# samd21_sensorhub_Lite_TQFP32_1_2_0_feb20.net
KiCad netlist of a schematic drawn in EAGLE
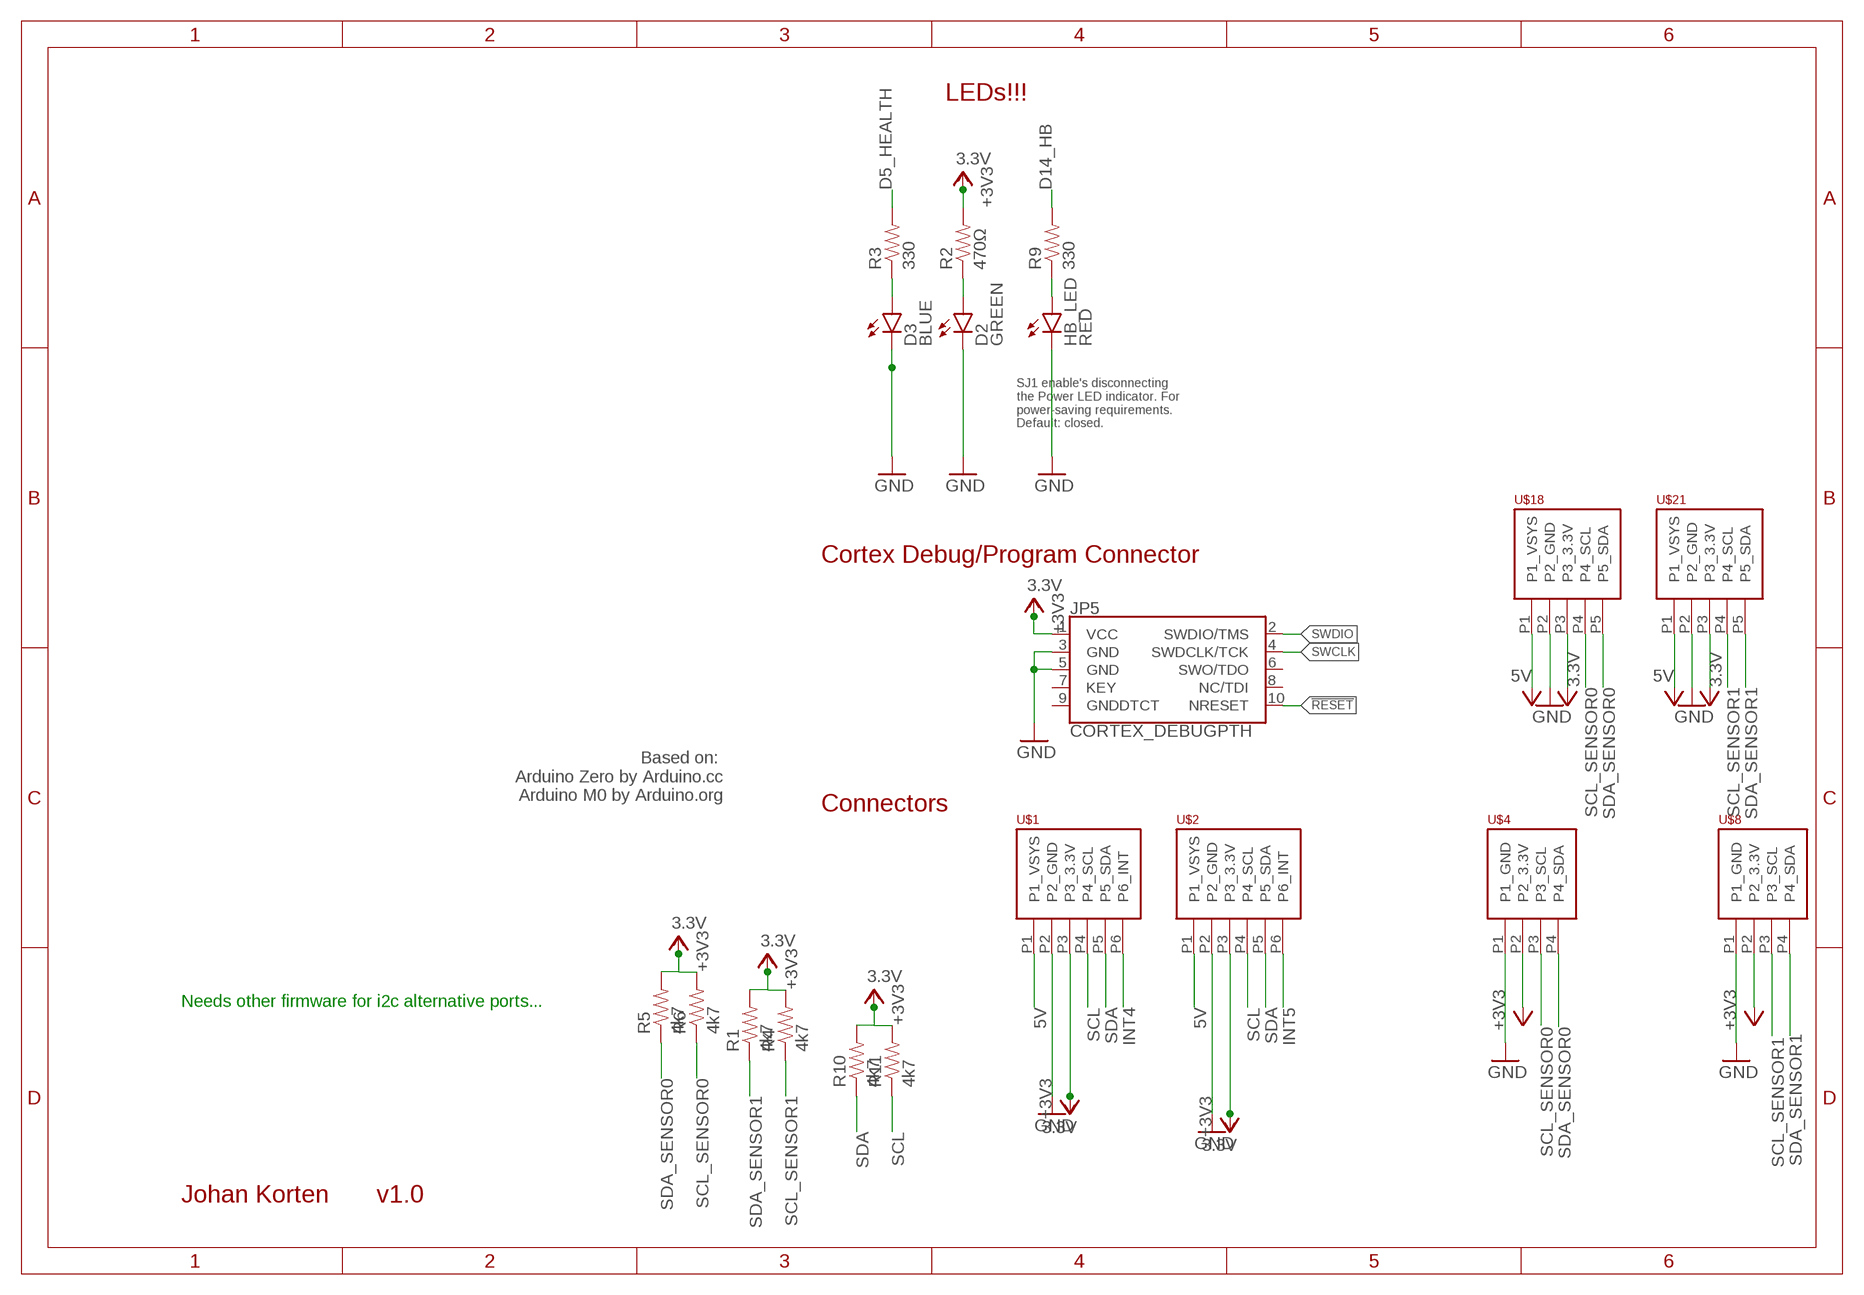
[diagram p0: schematic, sheet 1]
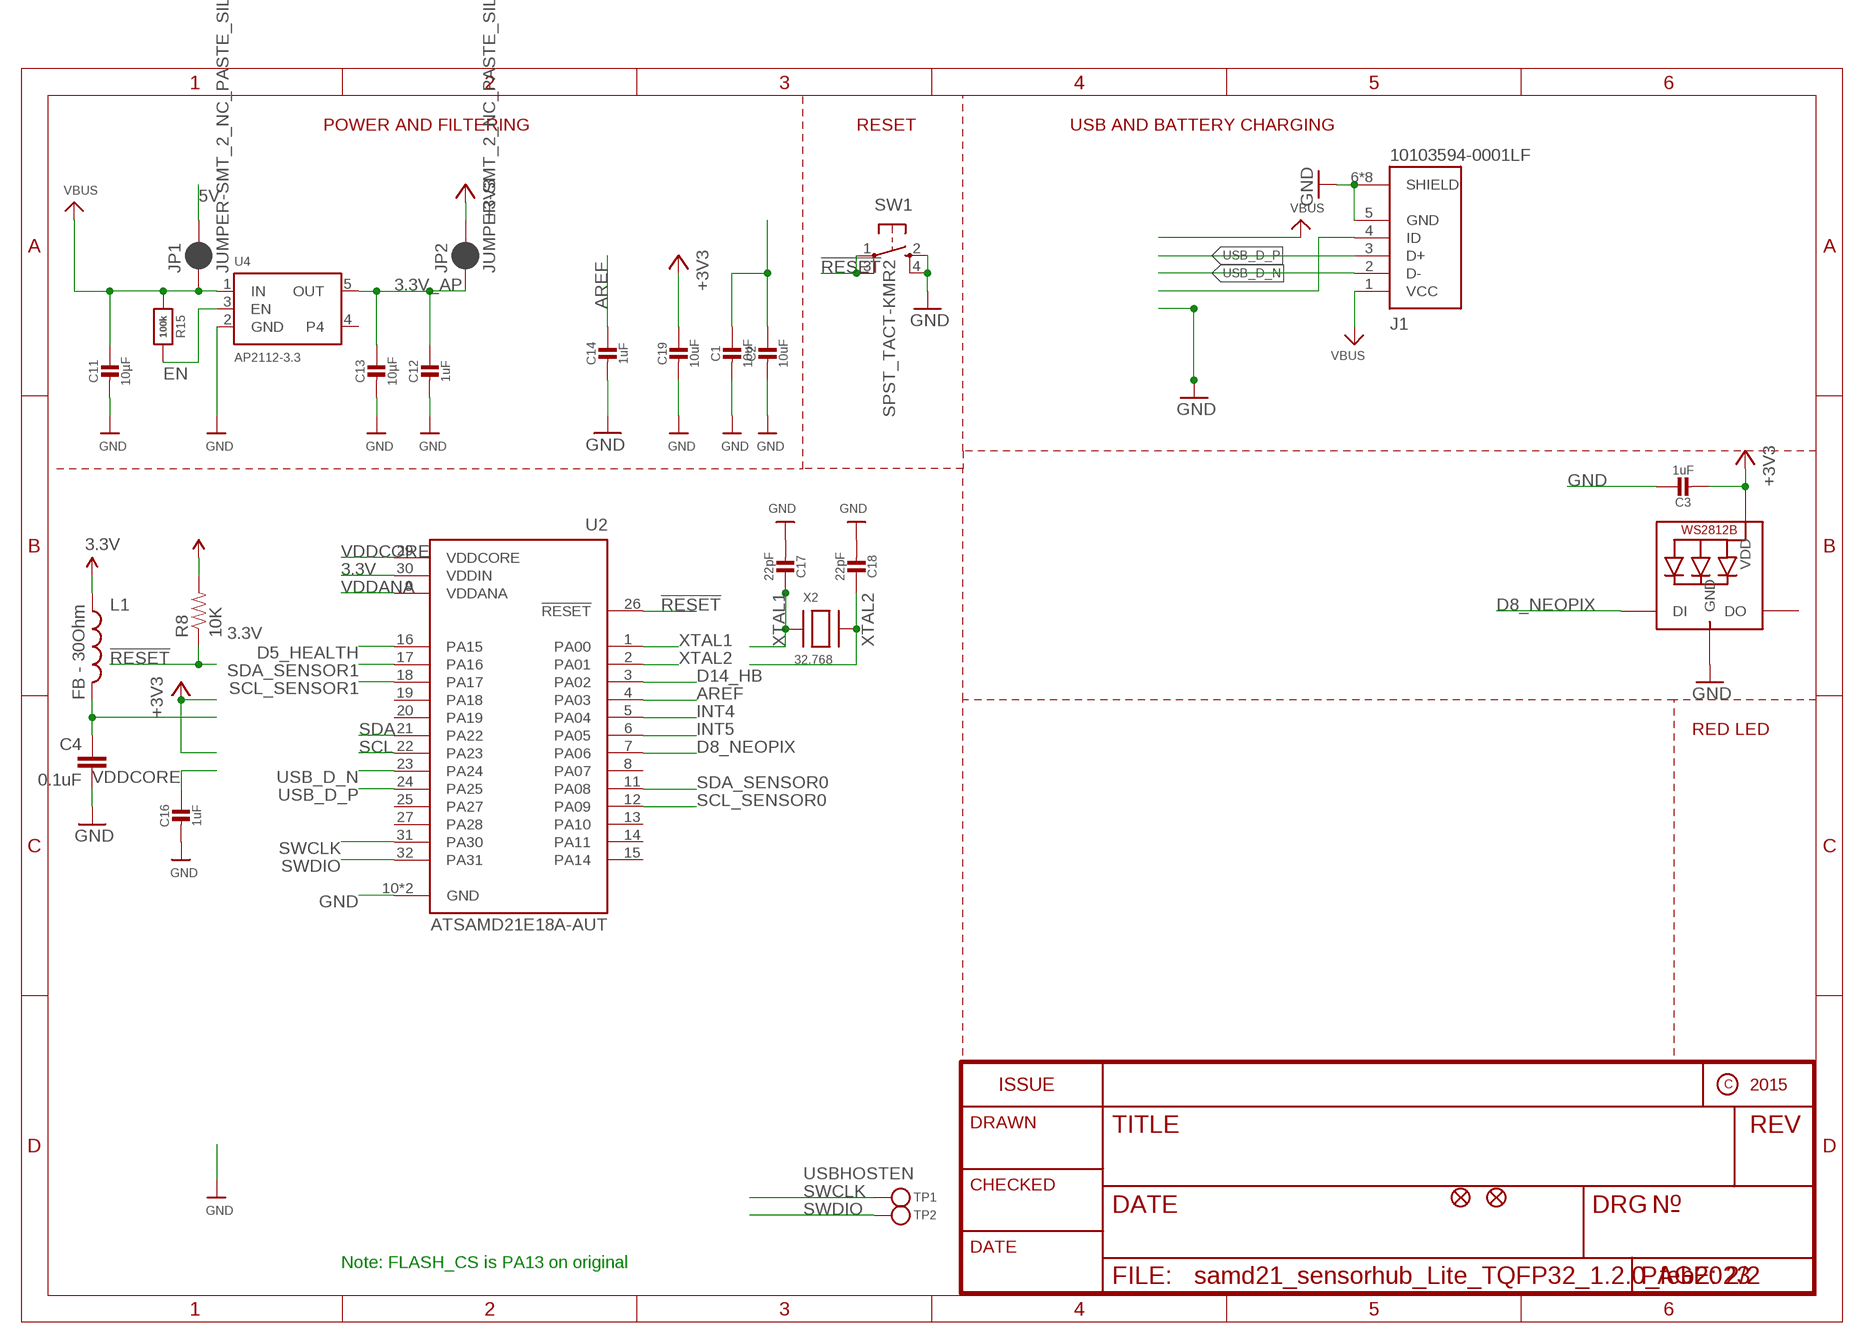
[diagram p1: schematic, sheet 2]

(export (version "E")
  (design (tool "Eeschema 10.0.6"))
  (components
    (comp (ref "C1")
      (value "10uF")
      (footprint "eagle-import:0805-NO")
      (libsource (lib "eagle-import") (part "CAP_CERAMIC0805-NOOUTLINE"))
    )
    (comp (ref "C2")
      (value "10uF")
      (footprint "eagle-import:0805-NO")
      (libsource (lib "eagle-import") (part "CAP_CERAMIC0805-NOOUTLINE"))
    )
    (comp (ref "C3")
      (value "1uF")
      (footprint "eagle-import:0603-NO")
      (libsource (lib "eagle-import") (part "CAP_CERAMIC0603_NO"))
    )
    (comp (ref "C4")
      (value "0.1uF")
      (footprint "eagle-import:0402-CAP")
      (libsource (lib "eagle-import") (part "0.1UF-16V(+-10%)(0402)"))
    )
    (comp (ref "C11")
      (value "10µF")
      (footprint "eagle-import:0805-NO")
      (libsource (lib "eagle-import") (part "CAP_CERAMIC0805-NOOUTLINE"))
    )
    (comp (ref "C12")
      (value "1uF")
      (footprint "eagle-import:0603-NO")
      (libsource (lib "eagle-import") (part "CAP_CERAMIC0603_NO"))
    )
    (comp (ref "C13")
      (value "10µF")
      (footprint "eagle-import:0805-NO")
      (libsource (lib "eagle-import") (part "CAP_CERAMIC0805-NOOUTLINE"))
    )
    (comp (ref "C14")
      (value "1uF")
      (footprint "eagle-import:0603-NO")
      (libsource (lib "eagle-import") (part "CAP_CERAMIC0603_NO"))
    )
    (comp (ref "C16")
      (value "1uF")
      (footprint "eagle-import:0603-NO")
      (libsource (lib "eagle-import") (part "CAP_CERAMIC0603_NO"))
    )
    (comp (ref "C17")
      (value "22pF")
      (footprint "eagle-import:0603-NO")
      (libsource (lib "eagle-import") (part "CAP_CERAMIC0603_NO"))
    )
    (comp (ref "C18")
      (value "22pF")
      (footprint "eagle-import:0603-NO")
      (libsource (lib "eagle-import") (part "CAP_CERAMIC0603_NO"))
    )
    (comp (ref "C19")
      (value "10uF")
      (footprint "eagle-import:0805-NO")
      (libsource (lib "eagle-import") (part "CAP_CERAMIC0805-NOOUTLINE"))
    )
    (comp (ref "J1")
      (value "10103594-0001LF")
      (footprint "eagle-import:AMPHENOL_10103594-0001LF")
      (fields (field (name "MF") "AMPHENOL ICC / FCI"))
      (libsource (lib "eagle-import") (part "10103594-0001LF"))
    )
    (comp (ref "JP1")
      (value "JUMPER-SMT_2_NC_PASTE_SILK")
      (footprint "eagle-import:SMT-JUMPER_2_NC_PASTE_SILK")
      (libsource (lib "eagle-import") (part "JUMPER-SMT_2_NC_PASTE_SILK"))
    )
    (comp (ref "JP2")
      (value "JUMPER-SMT_2_NC_PASTE_SILK")
      (footprint "eagle-import:SMT-JUMPER_2_NC_PASTE_SILK")
      (libsource (lib "eagle-import") (part "JUMPER-SMT_2_NC_PASTE_SILK"))
    )
    (comp (ref "L1")
      (value "FB - 30Ohm")
      (footprint "eagle-import:0603")
      (libsource (lib "eagle-import") (part "INDUCTOR0603"))
    )
    (comp (ref "LED1")
      (value "WS2812B3535")
      (footprint "eagle-import:LED3535")
      (libsource (lib "eagle-import") (part "WS2812B3535"))
    )
    (comp (ref "R8")
      (value "10K")
      (footprint "eagle-import:0603-RES")
      (libsource (lib "eagle-import") (part "10KOHM-1/10W-1%(0603)0603"))
    )
    (comp (ref "R15")
      (value "100k")
      (footprint "eagle-import:0603-NO")
      (libsource (lib "eagle-import") (part "RESISTOR_0603_NOOUT"))
    )
    (comp (ref "SW1")
      (value "SPST_TACT-KMR2")
      (footprint "eagle-import:KMR2")
      (libsource (lib "eagle-import") (part "SPST_TACT-KMR2"))
    )
    (comp (ref "TP1")
      (value "TESTPOINTROUND1.5MM")
      (footprint "eagle-import:TESTPOINT_ROUND_1.5MM")
      (libsource (lib "eagle-import") (part "TESTPOINTROUND1.5MM"))
    )
    (comp (ref "TP2")
      (value "TESTPOINTROUND1.5MM")
      (footprint "eagle-import:TESTPOINT_ROUND_1.5MM")
      (libsource (lib "eagle-import") (part "TESTPOINTROUND1.5MM"))
    )
    (comp (ref "U$34")
      (value "FIDUCIAL\"\"")
      (footprint "eagle-import:FIDUCIAL_1MM")
      (libsource (lib "eagle-import") (part "FIDUCIAL{dblquote}{dblquote}"))
    )
    (comp (ref "U$35")
      (value "FIDUCIAL\"\"")
      (footprint "eagle-import:FIDUCIAL_1MM")
      (libsource (lib "eagle-import") (part "FIDUCIAL{dblquote}{dblquote}"))
    )
    (comp (ref "U2")
      (value "ATSAMD21E18A-AUT")
      (footprint "eagle-import:QFP80P900X900X120-32N")
      (fields (field (name "MF") "Microchip") (field (name "MP") "ATSAMD21E18A-AU"))
      (libsource (lib "eagle-import") (part "ATSAMD21E18A-AUT"))
    )
    (comp (ref "U4")
      (value "AP2112-3.3")
      (footprint "eagle-import:SOT23-5")
      (libsource (lib "eagle-import") (part "VREG_SOT23-5"))
    )
    (comp (ref "X2")
      (value "32.768")
      (footprint "eagle-import:XTAL3215")
      (libsource (lib "eagle-import") (part "XTAL-3.2X1.5"))
    )
    (comp (ref "D2")
      (value "GREEN")
      (footprint "eagle-import:LED-0603")
      (libsource (lib "eagle-import") (part "LED-RED0603"))
    )
    (comp (ref "D3")
      (value "BLUE")
      (footprint "eagle-import:LED-0603")
      (libsource (lib "eagle-import") (part "LED-BLUE0603"))
    )
    (comp (ref "HB_LED")
      (value "RED")
      (footprint "eagle-import:LED-0603")
      (libsource (lib "eagle-import") (part "LED-RED0603"))
    )
    (comp (ref "JP5")
      (value "CORTEX_DEBUGPTH")
      (footprint "eagle-import:2X5-PTH-1.27MM")
      (libsource (lib "eagle-import") (part "CORTEX_DEBUGPTH"))
    )
    (comp (ref "R1")
      (value "4k7")
      (footprint "eagle-import:0603-RES")
      (libsource (lib "eagle-import") (part "330OHM1/10W1%(0603)"))
    )
    (comp (ref "R2")
      (value "470Ω")
      (footprint "eagle-import:0603-RES")
      (libsource (lib "eagle-import") (part "330OHM1/10W1%(0603)"))
    )
    (comp (ref "R3")
      (value "330")
      (footprint "eagle-import:0603-RES")
      (libsource (lib "eagle-import") (part "330OHM1/10W1%(0603)"))
    )
    (comp (ref "R4")
      (value "4k7")
      (footprint "eagle-import:0603-RES")
      (libsource (lib "eagle-import") (part "330OHM1/10W1%(0603)"))
    )
    (comp (ref "R5")
      (value "4k7")
      (footprint "eagle-import:0603-RES")
      (libsource (lib "eagle-import") (part "330OHM1/10W1%(0603)"))
    )
    (comp (ref "R6")
      (value "4k7")
      (footprint "eagle-import:0603-RES")
      (libsource (lib "eagle-import") (part "330OHM1/10W1%(0603)"))
    )
    (comp (ref "R9")
      (value "330")
      (footprint "eagle-import:0603-RES")
      (libsource (lib "eagle-import") (part "330OHM1/10W1%(0603)"))
    )
    (comp (ref "R10")
      (value "4k7")
      (footprint "eagle-import:0603-RES")
      (libsource (lib "eagle-import") (part "330OHM1/10W1%(0603)"))
    )
    (comp (ref "R11")
      (value "4k7")
      (footprint "eagle-import:0603-RES")
      (libsource (lib "eagle-import") (part "330OHM1/10W1%(0603)"))
    )
    (comp (ref "U$1")
      (value "PHOENIX_PTSM_M6_TH_I2CPPANGLE")
      (footprint "eagle-import:PTSM_M6_THRHOLE")
      (libsource (lib "eagle-import") (part "PHOENIX_PTSM_M6_TH_I2CPPANGLE"))
    )
    (comp (ref "U$2")
      (value "PHOENIX_PTSM_M6_TH_I2CPPANGLE")
      (footprint "eagle-import:PTSM_M6_THRHOLE")
      (libsource (lib "eagle-import") (part "PHOENIX_PTSM_M6_TH_I2CPPANGLE"))
    )
    (comp (ref "U$4")
      (value "PHOENIX_PTSM_M4_THANGLE")
      (footprint "eagle-import:PTSM_M4_TH")
      (libsource (lib "eagle-import") (part "PHOENIX_PTSM_M4_THANGLE"))
    )
    (comp (ref "U$8")
      (value "PHOENIX_PTSM_M4_THANGLE")
      (footprint "eagle-import:PTSM_M4_TH")
      (libsource (lib "eagle-import") (part "PHOENIX_PTSM_M4_THANGLE"))
    )
    (comp (ref "U$18")
      (value "PHOENIX_PTSM_M5_TH_I2C++")
      (footprint "eagle-import:PTSM_M5_THRHOLE")
      (libsource (lib "eagle-import") (part "PHOENIX_PTSM_M5_TH_I2C++"))
    )
    (comp (ref "U$21")
      (value "PHOENIX_PTSM_M5_TH_I2C++")
      (footprint "eagle-import:PTSM_M5_THRHOLE")
      (libsource (lib "eagle-import") (part "PHOENIX_PTSM_M5_TH_I2C++"))
    )
  )
  (nets
    (net (code "1") (name "3.3V") (class "Default")
      (node (ref "C19") (pin "1") (pinfunction "1_1") (pintype "passive"))
      (node (ref "C3") (pin "2") (pinfunction "2_2") (pintype "passive"))
      (node (ref "JP2") (pin "2") (pinfunction "2_2") (pintype "passive"))
      (node (ref "JP5") (pin "1") (pinfunction "VCC_1") (pintype "bidirectional"))
      (node (ref "L1") (pin "1") (pinfunction "1_1") (pintype "passive"))
      (node (ref "LED1") (pin "2") (pinfunction "VDD_2") (pintype "power_in"))
      (node (ref "R1") (pin "2") (pinfunction "2_2") (pintype "passive"))
      (node (ref "R10") (pin "2") (pinfunction "2_2") (pintype "passive"))
      (node (ref "R11") (pin "2") (pinfunction "2_2") (pintype "passive"))
      (node (ref "R2") (pin "2") (pinfunction "2_2") (pintype "passive"))
      (node (ref "R4") (pin "2") (pinfunction "2_2") (pintype "passive"))
      (node (ref "R5") (pin "2") (pinfunction "2_2") (pintype "passive"))
      (node (ref "R6") (pin "2") (pinfunction "2_2") (pintype "passive"))
      (node (ref "R8") (pin "2") (pinfunction "2_2") (pintype "passive"))
      (node (ref "U$1") (pin "P3") (pinfunction "P3_3.3V_P3") (pintype "power_in"))
      (node (ref "U$18") (pin "P3") (pinfunction "P3_3.3V_P3") (pintype "power_in"))
      (node (ref "U$2") (pin "P3") (pinfunction "P3_3.3V_P3") (pintype "power_in"))
      (node (ref "U$21") (pin "P3") (pinfunction "P3_3.3V_P3") (pintype "power_in"))
      (node (ref "U$4") (pin "P2") (pinfunction "P2_3.3V_P2") (pintype "power_in"))
      (node (ref "U$8") (pin "P2") (pinfunction "P2_3.3V_P2") (pintype "power_in"))
      (node (ref "U2") (pin "30") (pinfunction "VDDIN_30") (pintype "power_in"))
    )
    (net (code "2") (name "3.3V_AP") (class "Default")
      (node (ref "C12") (pin "1") (pinfunction "1_1") (pintype "passive"))
      (node (ref "C13") (pin "1") (pinfunction "1_1") (pintype "passive"))
      (node (ref "JP2") (pin "1") (pinfunction "1_1") (pintype "passive"))
      (node (ref "U4") (pin "5") (pinfunction "OUT_5") (pintype "power_in"))
    )
    (net (code "3") (name "5V") (class "Default")
      (node (ref "C1") (pin "1") (pinfunction "1_1") (pintype "passive"))
      (node (ref "C2") (pin "1") (pinfunction "1_1") (pintype "passive"))
      (node (ref "JP1") (pin "2") (pinfunction "2_2") (pintype "passive"))
      (node (ref "U$1") (pin "P1") (pinfunction "P1_VSYS_P1") (pintype "power_in"))
      (node (ref "U$18") (pin "P1") (pinfunction "P1_VSYS_P1") (pintype "power_in"))
      (node (ref "U$2") (pin "P1") (pinfunction "P1_VSYS_P1") (pintype "power_in"))
      (node (ref "U$21") (pin "P1") (pinfunction "P1_VSYS_P1") (pintype "power_in"))
    )
    (net (code "4") (name "AREF") (class "Default")
      (node (ref "C14") (pin "1") (pinfunction "1_1") (pintype "passive"))
      (node (ref "U2") (pin "4") (pinfunction "PA03_4") (pintype "bidirectional"))
    )
    (net (code "5") (name "D5_HEALTH") (class "Default")
      (node (ref "R3") (pin "2") (pinfunction "2_2") (pintype "passive"))
      (node (ref "U2") (pin "16") (pinfunction "PA15_16") (pintype "bidirectional"))
    )
    (net (code "6") (name "D8_NEOPIX") (class "Default")
      (node (ref "LED1") (pin "1") (pinfunction "DI_1") (pintype "input"))
      (node (ref "U2") (pin "7") (pinfunction "PA06_7") (pintype "bidirectional"))
    )
    (net (code "7") (name "D14_HB") (class "Default")
      (node (ref "R9") (pin "2") (pinfunction "2_2") (pintype "passive"))
      (node (ref "U2") (pin "3") (pinfunction "PA02_3") (pintype "bidirectional"))
    )
    (net (code "8") (name "EN") (class "Default")
      (node (ref "R15") (pin "2") (pinfunction "2_2") (pintype "passive"))
      (node (ref "U4") (pin "3") (pinfunction "EN_3") (pintype "input"))
    )
    (net (code "9") (name "GND") (class "Default")
      (node (ref "C1") (pin "2") (pinfunction "2_2") (pintype "passive"))
      (node (ref "C11") (pin "2") (pinfunction "2_2") (pintype "passive"))
      (node (ref "C12") (pin "2") (pinfunction "2_2") (pintype "passive"))
      (node (ref "C13") (pin "2") (pinfunction "2_2") (pintype "passive"))
      (node (ref "C14") (pin "2") (pinfunction "2_2") (pintype "passive"))
      (node (ref "C16") (pin "2") (pinfunction "2_2") (pintype "passive"))
      (node (ref "C17") (pin "2") (pinfunction "2_2") (pintype "passive"))
      (node (ref "C18") (pin "2") (pinfunction "2_2") (pintype "passive"))
      (node (ref "C19") (pin "2") (pinfunction "2_2") (pintype "passive"))
      (node (ref "C2") (pin "2") (pinfunction "2_2") (pintype "passive"))
      (node (ref "C3") (pin "1") (pinfunction "1_1") (pintype "passive"))
      (node (ref "C4") (pin "2") (pinfunction "2_2") (pintype "passive"))
      (node (ref "D2") (pin "C") (pinfunction "C_C") (pintype "passive"))
      (node (ref "D3") (pin "C") (pinfunction "C_C") (pintype "passive"))
      (node (ref "HB_LED") (pin "C") (pinfunction "C_C") (pintype "passive"))
      (node (ref "J1") (pin "10") (pinfunction "SHIELD_10") (pintype "passive"))
      (node (ref "J1") (pin "11") (pinfunction "SHIELD_11") (pintype "passive"))
      (node (ref "J1") (pin "5") (pinfunction "GND_5") (pintype "power_in"))
      (node (ref "J1") (pin "6") (pinfunction "SHIELD_6") (pintype "passive"))
      (node (ref "J1") (pin "7") (pinfunction "SHIELD_7") (pintype "passive"))
      (node (ref "J1") (pin "8") (pinfunction "SHIELD_8") (pintype "passive"))
      (node (ref "J1") (pin "9") (pinfunction "SHIELD_9") (pintype "passive"))
      (node (ref "J1") (pin "S1") (pinfunction "SHIELD_S1") (pintype "passive"))
      (node (ref "J1") (pin "S2") (pinfunction "SHIELD_S2") (pintype "passive"))
      (node (ref "JP5") (pin "3") (pinfunction "GND_3") (pintype "bidirectional"))
      (node (ref "JP5") (pin "5") (pinfunction "GND_5") (pintype "bidirectional"))
      (node (ref "LED1") (pin "4") (pinfunction "GND_4") (pintype "power_in"))
      (node (ref "SW1") (pin "2") (pinfunction "S_2") (pintype "passive"))
      (node (ref "SW1") (pin "4") (pinfunction "S1_4") (pintype "passive"))
      (node (ref "U$1") (pin "P2") (pinfunction "P2_GND_P2") (pintype "power_in"))
      (node (ref "U$18") (pin "P2") (pinfunction "P2_GND_P2") (pintype "power_in"))
      (node (ref "U$2") (pin "P2") (pinfunction "P2_GND_P2") (pintype "power_in"))
      (node (ref "U$21") (pin "P2") (pinfunction "P2_GND_P2") (pintype "power_in"))
      (node (ref "U$4") (pin "P1") (pinfunction "P1_GND_P1") (pintype "power_in"))
      (node (ref "U$8") (pin "P1") (pinfunction "P1_GND_P1") (pintype "power_in"))
      (node (ref "U2") (pin "10") (pinfunction "GND_10") (pintype "power_in"))
      (node (ref "U2") (pin "28") (pinfunction "GND_28") (pintype "power_in"))
      (node (ref "U4") (pin "2") (pinfunction "GND_2") (pintype "power_in"))
    )
    (net (code "10") (name "INT4") (class "Default")
      (node (ref "U$1") (pin "P6") (pinfunction "P6_INT_P6") (pintype "power_in"))
      (node (ref "U2") (pin "5") (pinfunction "PA04_5") (pintype "bidirectional"))
    )
    (net (code "11") (name "INT5") (class "Default")
      (node (ref "U$2") (pin "P6") (pinfunction "P6_INT_P6") (pintype "power_in"))
      (node (ref "U2") (pin "6") (pinfunction "PA05_6") (pintype "bidirectional"))
    )
    (net (code "12") (name "Net-(D2-PadA)") (class "Default")
      (node (ref "D2") (pin "A") (pinfunction "A_A") (pintype "passive"))
      (node (ref "R2") (pin "1") (pinfunction "1_1") (pintype "passive"))
    )
    (net (code "13") (name "Net-(D3-PadA)") (class "Default")
      (node (ref "D3") (pin "A") (pinfunction "A_A") (pintype "passive"))
      (node (ref "R3") (pin "1") (pinfunction "1_1") (pintype "passive"))
    )
    (net (code "14") (name "Net-(HB_LED-PadA)") (class "Default")
      (node (ref "HB_LED") (pin "A") (pinfunction "A_A") (pintype "passive"))
      (node (ref "R9") (pin "1") (pinfunction "1_1") (pintype "passive"))
    )
    (net (code "15") (name "SCL") (class "Default")
      (node (ref "R11") (pin "1") (pinfunction "1_1") (pintype "passive"))
      (node (ref "U$1") (pin "P4") (pinfunction "P4_SCL_P4") (pintype "bidirectional"))
      (node (ref "U$2") (pin "P4") (pinfunction "P4_SCL_P4") (pintype "bidirectional"))
      (node (ref "U2") (pin "22") (pinfunction "PA23_22") (pintype "bidirectional"))
    )
    (net (code "16") (name "SCL_SENSOR0") (class "Default")
      (node (ref "R6") (pin "1") (pinfunction "1_1") (pintype "passive"))
      (node (ref "U$18") (pin "P4") (pinfunction "P4_SCL_P4") (pintype "bidirectional"))
      (node (ref "U$4") (pin "P3") (pinfunction "P3_SCL_P3") (pintype "bidirectional"))
      (node (ref "U2") (pin "12") (pinfunction "PA09_12") (pintype "bidirectional"))
    )
    (net (code "17") (name "SCL_SENSOR1") (class "Default")
      (node (ref "R4") (pin "1") (pinfunction "1_1") (pintype "passive"))
      (node (ref "U$21") (pin "P4") (pinfunction "P4_SCL_P4") (pintype "bidirectional"))
      (node (ref "U$8") (pin "P3") (pinfunction "P3_SCL_P3") (pintype "bidirectional"))
      (node (ref "U2") (pin "18") (pinfunction "PA17_18") (pintype "bidirectional"))
    )
    (net (code "18") (name "SDA") (class "Default")
      (node (ref "R10") (pin "1") (pinfunction "1_1") (pintype "passive"))
      (node (ref "U$1") (pin "P5") (pinfunction "P5_SDA_P5") (pintype "bidirectional"))
      (node (ref "U$2") (pin "P5") (pinfunction "P5_SDA_P5") (pintype "bidirectional"))
      (node (ref "U2") (pin "21") (pinfunction "PA22_21") (pintype "bidirectional"))
    )
    (net (code "19") (name "SDA_SENSOR0") (class "Default")
      (node (ref "R5") (pin "1") (pinfunction "1_1") (pintype "passive"))
      (node (ref "U$18") (pin "P5") (pinfunction "P5_SDA_P5") (pintype "bidirectional"))
      (node (ref "U$4") (pin "P4") (pinfunction "P4_SDA_P4") (pintype "bidirectional"))
      (node (ref "U2") (pin "11") (pinfunction "PA08_11") (pintype "bidirectional"))
    )
    (net (code "20") (name "SDA_SENSOR1") (class "Default")
      (node (ref "R1") (pin "1") (pinfunction "1_1") (pintype "passive"))
      (node (ref "U$21") (pin "P5") (pinfunction "P5_SDA_P5") (pintype "bidirectional"))
      (node (ref "U$8") (pin "P4") (pinfunction "P4_SDA_P4") (pintype "bidirectional"))
      (node (ref "U2") (pin "17") (pinfunction "PA16_17") (pintype "bidirectional"))
    )
    (net (code "21") (name "SWCLK") (class "Default")
      (node (ref "JP5") (pin "4") (pinfunction "SWDCLK/TCK_4") (pintype "bidirectional"))
      (node (ref "TP1") (pin "P$1") (pinfunction "P$1_P$1") (pintype "bidirectional"))
      (node (ref "U2") (pin "31") (pinfunction "PA30_31") (pintype "bidirectional"))
    )
    (net (code "22") (name "SWDIO") (class "Default")
      (node (ref "JP5") (pin "2") (pinfunction "SWDIO/TMS_2") (pintype "bidirectional"))
      (node (ref "TP2") (pin "P$1") (pinfunction "P$1_P$1") (pintype "bidirectional"))
      (node (ref "U2") (pin "32") (pinfunction "PA31_32") (pintype "bidirectional"))
    )
    (net (code "23") (name "USB_D_N") (class "Default")
      (node (ref "J1") (pin "2") (pinfunction "D-_2") (pintype "bidirectional"))
      (node (ref "U2") (pin "23") (pinfunction "PA24_23") (pintype "bidirectional"))
    )
    (net (code "24") (name "USB_D_P") (class "Default")
      (node (ref "J1") (pin "3") (pinfunction "D+_3") (pintype "bidirectional"))
      (node (ref "U2") (pin "24") (pinfunction "PA25_24") (pintype "bidirectional"))
    )
    (net (code "25") (name "VBUS") (class "Default")
      (node (ref "C11") (pin "1") (pinfunction "1_1") (pintype "passive"))
      (node (ref "J1") (pin "1") (pinfunction "VCC_1") (pintype "power_in"))
      (node (ref "JP1") (pin "1") (pinfunction "1_1") (pintype "passive"))
      (node (ref "R15") (pin "1") (pinfunction "1_1") (pintype "passive"))
      (node (ref "U4") (pin "1") (pinfunction "IN_1") (pintype "power_in"))
    )
    (net (code "26") (name "VDDANA") (class "Default")
      (node (ref "C4") (pin "1") (pinfunction "1_1") (pintype "passive"))
      (node (ref "L1") (pin "2") (pinfunction "2_2") (pintype "passive"))
      (node (ref "U2") (pin "9") (pinfunction "VDDANA_9") (pintype "power_in"))
    )
    (net (code "27") (name "VDDCORE") (class "Default")
      (node (ref "C16") (pin "1") (pinfunction "1_1") (pintype "passive"))
      (node (ref "U2") (pin "29") (pinfunction "VDDCORE_29") (pintype "power_in"))
    )
    (net (code "28") (name "XTAL1") (class "Default")
      (node (ref "C17") (pin "1") (pinfunction "1_1") (pintype "passive"))
      (node (ref "U2") (pin "1") (pinfunction "PA00_1") (pintype "bidirectional"))
      (node (ref "X2") (pin "P$1") (pinfunction "P$1_P$1") (pintype "bidirectional"))
    )
    (net (code "29") (name "XTAL2") (class "Default")
      (node (ref "C18") (pin "1") (pinfunction "1_1") (pintype "passive"))
      (node (ref "U2") (pin "2") (pinfunction "PA01_2") (pintype "bidirectional"))
      (node (ref "X2") (pin "P$2") (pinfunction "P$2_P$2") (pintype "bidirectional"))
    )
    (net (code "30") (name "unconnected-(J1-ID-Pad4)") (class "Default")
      (node (ref "J1") (pin "4") (pinfunction "ID_4") (pintype "bidirectional"))
    )
    (net (code "31") (name "unconnected-(JP5-GNDDTCT-Pad9)") (class "Default")
      (node (ref "JP5") (pin "9") (pinfunction "GNDDTCT_9") (pintype "bidirectional"))
    )
    (net (code "32") (name "unconnected-(JP5-KEY-Pad7)") (class "Default")
      (node (ref "JP5") (pin "7") (pinfunction "KEY_7") (pintype "bidirectional"))
    )
    (net (code "33") (name "unconnected-(JP5-NC{slash}TDI-Pad8)") (class "Default")
      (node (ref "JP5") (pin "8") (pinfunction "NC/TDI_8") (pintype "bidirectional"))
    )
    (net (code "34") (name "unconnected-(JP5-SWO{slash}TDO-Pad6)") (class "Default")
      (node (ref "JP5") (pin "6") (pinfunction "SWO/TDO_6") (pintype "bidirectional"))
    )
    (net (code "35") (name "unconnected-(LED1-DO-Pad3)") (class "Default")
      (node (ref "LED1") (pin "3") (pinfunction "DO_3") (pintype "output"))
    )
    (net (code "36") (name "unconnected-(U2-PA07-Pad8)") (class "Default")
      (node (ref "U2") (pin "8") (pinfunction "PA07_8") (pintype "bidirectional"))
    )
    (net (code "37") (name "unconnected-(U2-PA10-Pad13)") (class "Default")
      (node (ref "U2") (pin "13") (pinfunction "PA10_13") (pintype "bidirectional"))
    )
    (net (code "38") (name "unconnected-(U2-PA11-Pad14)") (class "Default")
      (node (ref "U2") (pin "14") (pinfunction "PA11_14") (pintype "bidirectional"))
    )
    (net (code "39") (name "unconnected-(U2-PA14-Pad15)") (class "Default")
      (node (ref "U2") (pin "15") (pinfunction "PA14_15") (pintype "bidirectional"))
    )
    (net (code "40") (name "unconnected-(U2-PA18-Pad19)") (class "Default")
      (node (ref "U2") (pin "19") (pinfunction "PA18_19") (pintype "bidirectional"))
    )
    (net (code "41") (name "unconnected-(U2-PA19-Pad20)") (class "Default")
      (node (ref "U2") (pin "20") (pinfunction "PA19_20") (pintype "bidirectional"))
    )
    (net (code "42") (name "unconnected-(U2-PA27-Pad25)") (class "Default")
      (node (ref "U2") (pin "25") (pinfunction "PA27_25") (pintype "bidirectional"))
    )
    (net (code "43") (name "unconnected-(U2-PA28-Pad27)") (class "Default")
      (node (ref "U2") (pin "27") (pinfunction "PA28_27") (pintype "bidirectional"))
    )
    (net (code "44") (name "unconnected-(U4-P4-Pad4)") (class "Default")
      (node (ref "U4") (pin "4") (pinfunction "P4_4") (pintype "bidirectional"))
    )
    (net (code "45") (name "~{RESET}") (class "Default")
      (node (ref "JP5") (pin "10") (pinfunction "NRESET_10") (pintype "bidirectional"))
      (node (ref "R8") (pin "1") (pinfunction "1_1") (pintype "passive"))
      (node (ref "SW1") (pin "1") (pinfunction "P_1") (pintype "passive"))
      (node (ref "SW1") (pin "3") (pinfunction "P1_3") (pintype "passive"))
      (node (ref "U2") (pin "26") (pinfunction "~{RESET}_26") (pintype "input"))
    )
  )
)
